# Projeto_Temperatura.net
KiCad netlist of a schematic drawn in EAGLE
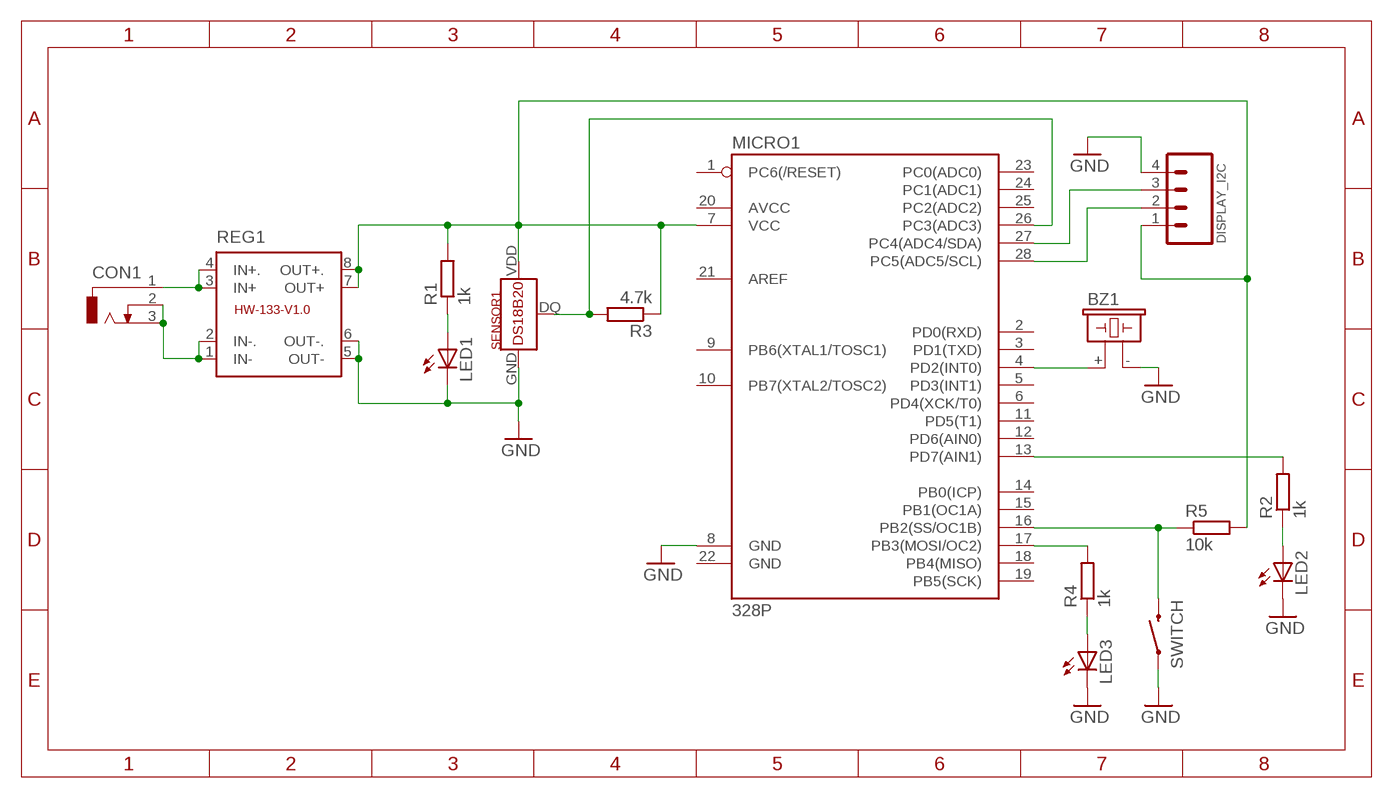
[diagram p0: schematic, sheet 1]

(export (version "E")
  (design (tool "Eeschema 10.0.6"))
  (components
    (comp (ref "BZ1")
      (value "F/CM12P")
      (footprint "eagle-import:F_CM12P")
      (libsource (lib "eagle-import") (part "F/CM12P"))
    )
    (comp (ref "CON1")
      (value "DCJ0202")
      (footprint "eagle-import:DCJ0202")
      (libsource (lib "eagle-import") (part "DCJ0202"))
    )
    (comp (ref "DISPLAY_I2C")
      (value "MA04")
      (footprint "eagle-import:04PA")
      (libsource (lib "eagle-import") (part "MA04"))
    )
    (comp (ref "LED1")
      (value "LED5MM")
      (footprint "eagle-import:LED5MM")
      (libsource (lib "eagle-import") (part "LED5MM"))
    )
    (comp (ref "LED2")
      (value "LED5MM")
      (footprint "eagle-import:LED5MM")
      (libsource (lib "eagle-import") (part "LED5MM"))
    )
    (comp (ref "LED3")
      (value "LED5MM")
      (footprint "eagle-import:LED5MM")
      (libsource (lib "eagle-import") (part "LED5MM"))
    )
    (comp (ref "MICRO1")
      (value "328P")
      (footprint "eagle-import:DIP28")
      (libsource (lib "eagle-import") (part "ATMEGA328P_PDIP"))
    )
    (comp (ref "R1")
      (value "1k")
      (footprint "eagle-import:0204_7")
      (libsource (lib "eagle-import") (part "R-EU_0204/7"))
    )
    (comp (ref "R2")
      (value "1k")
      (footprint "eagle-import:0204_7")
      (libsource (lib "eagle-import") (part "R-EU_0204/7"))
    )
    (comp (ref "R3")
      (value "4.7k")
      (footprint "eagle-import:0204_7")
      (libsource (lib "eagle-import") (part "R-EU_0204/7"))
    )
    (comp (ref "R4")
      (value "1k")
      (footprint "eagle-import:0204_7")
      (libsource (lib "eagle-import") (part "R-EU_0204/7"))
    )
    (comp (ref "R5")
      (value "10k")
      (footprint "eagle-import:0204_7")
      (libsource (lib "eagle-import") (part "R-EU_0204/7"))
    )
    (comp (ref "REG1")
      (value "REGULADOR")
      (footprint "eagle-import:REGULADOR")
      (libsource (lib "eagle-import") (part "REGULADOR"))
    )
    (comp (ref "SENSOR1")
      (value "DS18B20")
      (footprint "eagle-import:TO-92")
      (libsource (lib "eagle-import") (part "DS18B20"))
    )
    (comp (ref "SWITCH")
      (value "MOMENTARY-SWITCH-SPST-PTH-RIGHT-ANGLE-KIT")
      (footprint "eagle-import:TACTILE_SWITCH_PTH_RIGHT_ANGLE_KIT")
      (libsource (lib "eagle-import") (part "MOMENTARY-SWITCH-SPST-PTH-RIGHT-ANGLE-KIT"))
    )
  )
  (nets
    (net (code "1") (name "GND") (class "Default")
      (node (ref "BZ1") (pin "-") (pinfunction "2_-") (pintype "passive"))
      (node (ref "DISPLAY_I2C") (pin "4") (pinfunction "4_4") (pintype "passive"))
      (node (ref "LED1") (pin "K") (pinfunction "C_K") (pintype "passive"))
      (node (ref "LED2") (pin "K") (pinfunction "C_K") (pintype "passive"))
      (node (ref "LED3") (pin "K") (pinfunction "C_K") (pintype "passive"))
      (node (ref "MICRO1") (pin "8") (pinfunction "GND_8") (pintype "bidirectional"))
      (node (ref "REG1") (pin "5") (pinfunction "OUT-_5") (pintype "output"))
      (node (ref "REG1") (pin "6") (pinfunction "OUT-._6") (pintype "output"))
      (node (ref "SENSOR1") (pin "GND") (pinfunction "1_GND") (pintype "power_in"))
      (node (ref "SWITCH") (pin "1") (pinfunction "1_1") (pintype "passive"))
    )
    (net (code "2") (name "Net-(BZ1-1)") (class "Default")
      (node (ref "BZ1") (pin "+") (pinfunction "1_+") (pintype "passive"))
      (node (ref "MICRO1") (pin "4") (pinfunction "PD2(INT0)_4") (pintype "bidirectional"))
    )
    (net (code "3") (name "Net-(LED1-PadA)") (class "Default")
      (node (ref "LED1") (pin "A") (pinfunction "A_A") (pintype "passive"))
      (node (ref "R1") (pin "1") (pinfunction "1_1") (pintype "passive"))
    )
    (net (code "4") (name "Net-(LED2-PadA)") (class "Default")
      (node (ref "LED2") (pin "A") (pinfunction "A_A") (pintype "passive"))
      (node (ref "R2") (pin "1") (pinfunction "1_1") (pintype "passive"))
    )
    (net (code "5") (name "Net-(LED3-PadA)") (class "Default")
      (node (ref "LED3") (pin "A") (pinfunction "A_A") (pintype "passive"))
      (node (ref "R4") (pin "1") (pinfunction "1_1") (pintype "passive"))
    )
    (net (code "6") (name "Net-(MICRO1-PB2(SS{slash}OC1B))") (class "Default")
      (node (ref "MICRO1") (pin "16") (pinfunction "PB2(SS/OC1B)_16") (pintype "bidirectional"))
      (node (ref "R5") (pin "1") (pinfunction "1_1") (pintype "passive"))
      (node (ref "SWITCH") (pin "2") (pinfunction "2_2") (pintype "passive"))
    )
    (net (code "7") (name "Net-(MICRO1-PB3(MOSI{slash}OC2))") (class "Default")
      (node (ref "MICRO1") (pin "17") (pinfunction "PB3(MOSI/OC2)_17") (pintype "bidirectional"))
      (node (ref "R4") (pin "2") (pinfunction "2_2") (pintype "passive"))
    )
    (net (code "8") (name "Net-(MICRO1-PC3(ADC3))") (class "Default")
      (node (ref "MICRO1") (pin "26") (pinfunction "PC3(ADC3)_26") (pintype "bidirectional"))
      (node (ref "R3") (pin "2") (pinfunction "2_2") (pintype "passive"))
      (node (ref "SENSOR1") (pin "DQ") (pinfunction "2_DQ") (pintype "tri_state"))
    )
    (net (code "9") (name "Net-(MICRO1-PC4(ADC4{slash}SDA))") (class "Default")
      (node (ref "DISPLAY_I2C") (pin "3") (pinfunction "3_3") (pintype "passive"))
      (node (ref "MICRO1") (pin "27") (pinfunction "PC4(ADC4/SDA)_27") (pintype "bidirectional"))
    )
    (net (code "10") (name "Net-(MICRO1-PC5(ADC5{slash}SCL))") (class "Default")
      (node (ref "DISPLAY_I2C") (pin "2") (pinfunction "2_2") (pintype "passive"))
      (node (ref "MICRO1") (pin "28") (pinfunction "PC5(ADC5/SCL)_28") (pintype "bidirectional"))
    )
    (net (code "11") (name "Net-(MICRO1-PD7(AIN1))") (class "Default")
      (node (ref "MICRO1") (pin "13") (pinfunction "PD7(AIN1)_13") (pintype "bidirectional"))
      (node (ref "R2") (pin "2") (pinfunction "2_2") (pintype "passive"))
    )
    (net (code "12") (name "Net-(MICRO1-VCC)") (class "Default")
      (node (ref "DISPLAY_I2C") (pin "1") (pinfunction "1_1") (pintype "passive"))
      (node (ref "MICRO1") (pin "7") (pinfunction "VCC_7") (pintype "bidirectional"))
      (node (ref "R1") (pin "2") (pinfunction "2_2") (pintype "passive"))
      (node (ref "R3") (pin "1") (pinfunction "1_1") (pintype "passive"))
      (node (ref "R5") (pin "2") (pinfunction "2_2") (pintype "passive"))
      (node (ref "REG1") (pin "7") (pinfunction "OUT+_7") (pintype "output"))
      (node (ref "REG1") (pin "8") (pinfunction "OUT+._8") (pintype "output"))
      (node (ref "SENSOR1") (pin "VDD") (pinfunction "3_VDD") (pintype "power_in"))
    )
    (net (code "13") (name "Net-(REG1-IN+)") (class "Default")
      (node (ref "CON1") (pin "1") (pinfunction "1_1") (pintype "passive"))
      (node (ref "REG1") (pin "3") (pinfunction "IN+_3") (pintype "power_in"))
      (node (ref "REG1") (pin "4") (pinfunction "IN+._4") (pintype "power_in"))
    )
    (net (code "14") (name "Net-(REG1-IN-)") (class "Default")
      (node (ref "CON1") (pin "2") (pinfunction "2_2") (pintype "passive"))
      (node (ref "CON1") (pin "3") (pinfunction "3_3") (pintype "passive"))
      (node (ref "REG1") (pin "1") (pinfunction "IN-_1") (pintype "power_in"))
      (node (ref "REG1") (pin "2") (pinfunction "IN-._2") (pintype "power_in"))
    )
    (net (code "15") (name "unconnected-(MICRO1-AREF-Pad21)") (class "Default")
      (node (ref "MICRO1") (pin "21") (pinfunction "AREF_21") (pintype "bidirectional"))
    )
    (net (code "16") (name "unconnected-(MICRO1-AVCC-Pad20)") (class "Default")
      (node (ref "MICRO1") (pin "20") (pinfunction "AVCC_20") (pintype "bidirectional"))
    )
    (net (code "17") (name "unconnected-(MICRO1-GND-Pad22)") (class "Default")
      (node (ref "MICRO1") (pin "22") (pinfunction "GND_22") (pintype "bidirectional"))
    )
    (net (code "18") (name "unconnected-(MICRO1-PB0(ICP)-Pad14)") (class "Default")
      (node (ref "MICRO1") (pin "14") (pinfunction "PB0(ICP)_14") (pintype "bidirectional"))
    )
    (net (code "19") (name "unconnected-(MICRO1-PB1(OC1A)-Pad15)") (class "Default")
      (node (ref "MICRO1") (pin "15") (pinfunction "PB1(OC1A)_15") (pintype "bidirectional"))
    )
    (net (code "20") (name "unconnected-(MICRO1-PB4(MISO)-Pad18)") (class "Default")
      (node (ref "MICRO1") (pin "18") (pinfunction "PB4(MISO)_18") (pintype "bidirectional"))
    )
    (net (code "21") (name "unconnected-(MICRO1-PB5(SCK)-Pad19)") (class "Default")
      (node (ref "MICRO1") (pin "19") (pinfunction "PB5(SCK)_19") (pintype "bidirectional"))
    )
    (net (code "22") (name "unconnected-(MICRO1-PB6(XTAL1{slash}TOSC1)-Pad9)") (class "Default")
      (node (ref "MICRO1") (pin "9") (pinfunction "PB6(XTAL1/TOSC1)_9") (pintype "bidirectional"))
    )
    (net (code "23") (name "unconnected-(MICRO1-PB7(XTAL2{slash}TOSC2)-Pad10)") (class "Default")
      (node (ref "MICRO1") (pin "10") (pinfunction "PB7(XTAL2/TOSC2)_10") (pintype "bidirectional"))
    )
    (net (code "24") (name "unconnected-(MICRO1-PC0(ADC0)-Pad23)") (class "Default")
      (node (ref "MICRO1") (pin "23") (pinfunction "PC0(ADC0)_23") (pintype "bidirectional"))
    )
    (net (code "25") (name "unconnected-(MICRO1-PC1(ADC1)-Pad24)") (class "Default")
      (node (ref "MICRO1") (pin "24") (pinfunction "PC1(ADC1)_24") (pintype "bidirectional"))
    )
    (net (code "26") (name "unconnected-(MICRO1-PC2(ADC2)-Pad25)") (class "Default")
      (node (ref "MICRO1") (pin "25") (pinfunction "PC2(ADC2)_25") (pintype "bidirectional"))
    )
    (net (code "27") (name "unconnected-(MICRO1-PC6({slash}RESET)-Pad1)") (class "Default")
      (node (ref "MICRO1") (pin "1") (pinfunction "PC6(/RESET)_1") (pintype "bidirectional"))
    )
    (net (code "28") (name "unconnected-(MICRO1-PD0(RXD)-Pad2)") (class "Default")
      (node (ref "MICRO1") (pin "2") (pinfunction "PD0(RXD)_2") (pintype "bidirectional"))
    )
    (net (code "29") (name "unconnected-(MICRO1-PD1(TXD)-Pad3)") (class "Default")
      (node (ref "MICRO1") (pin "3") (pinfunction "PD1(TXD)_3") (pintype "bidirectional"))
    )
    (net (code "30") (name "unconnected-(MICRO1-PD3(INT1)-Pad5)") (class "Default")
      (node (ref "MICRO1") (pin "5") (pinfunction "PD3(INT1)_5") (pintype "bidirectional"))
    )
    (net (code "31") (name "unconnected-(MICRO1-PD4(XCK{slash}T0)-Pad6)") (class "Default")
      (node (ref "MICRO1") (pin "6") (pinfunction "PD4(XCK/T0)_6") (pintype "bidirectional"))
    )
    (net (code "32") (name "unconnected-(MICRO1-PD5(T1)-Pad11)") (class "Default")
      (node (ref "MICRO1") (pin "11") (pinfunction "PD5(T1)_11") (pintype "bidirectional"))
    )
    (net (code "33") (name "unconnected-(MICRO1-PD6(AIN0)-Pad12)") (class "Default")
      (node (ref "MICRO1") (pin "12") (pinfunction "PD6(AIN0)_12") (pintype "bidirectional"))
    )
  )
)
